# upper.net
KiCad netlist of a schematic drawn in EAGLE
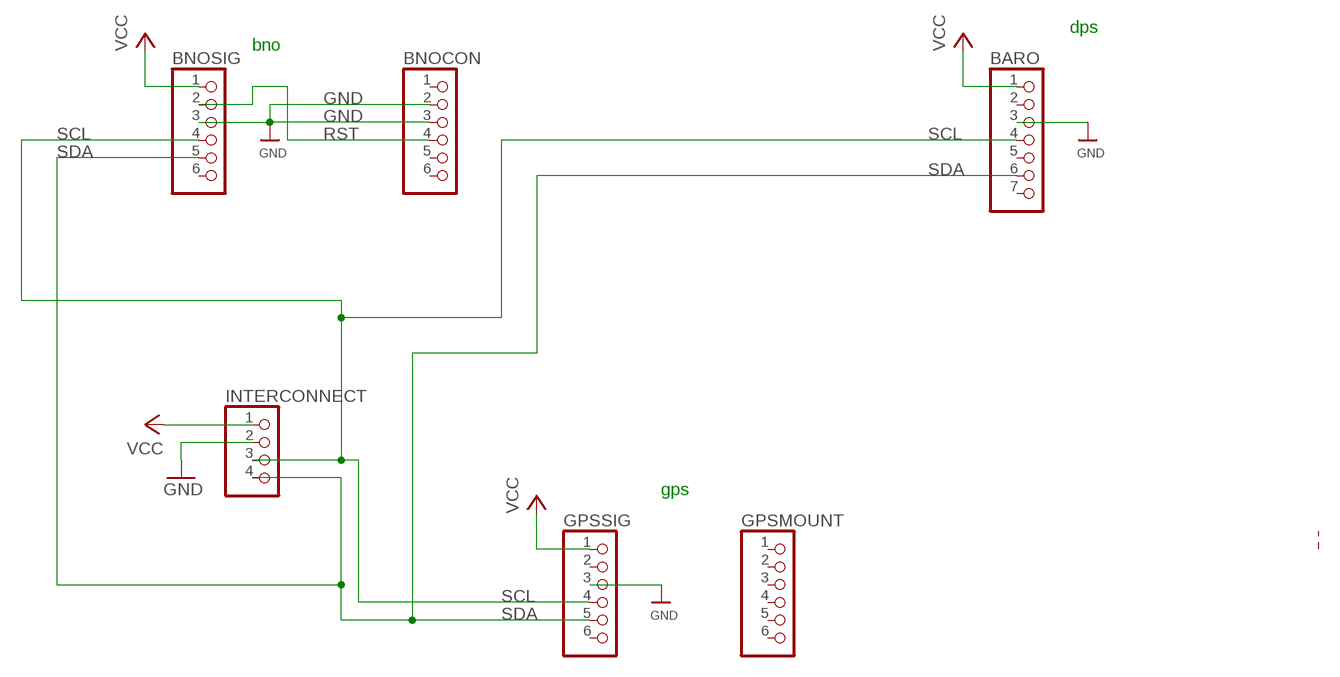
[diagram p0: schematic, sheet 1]

(export (version "E")
  (design (tool "Eeschema 10.0.6"))
  (components
    (comp (ref "BARO")
      (value "HEADER-1X770MIL")
      (footprint "eagle-import:1X07_ROUND_70")
      (libsource (lib "eagle-import") (part "HEADER-1X770MIL"))
    )
    (comp (ref "BNOCON")
      (value "HEADER-1X670MIL")
      (footprint "eagle-import:1X06_ROUND_70")
      (libsource (lib "eagle-import") (part "HEADER-1X670MIL"))
    )
    (comp (ref "BNOSIG")
      (value "HEADER-1X670MIL")
      (footprint "eagle-import:1X06_ROUND_70")
      (libsource (lib "eagle-import") (part "HEADER-1X670MIL"))
    )
    (comp (ref "GPSMOUNT")
      (value "HEADER-1X670MIL")
      (footprint "eagle-import:1X06_ROUND_70")
      (libsource (lib "eagle-import") (part "HEADER-1X670MIL"))
    )
    (comp (ref "GPSSIG")
      (value "HEADER-1X670MIL")
      (footprint "eagle-import:1X06_ROUND_70")
      (libsource (lib "eagle-import") (part "HEADER-1X670MIL"))
    )
    (comp (ref "INTERCONNECT")
      (value "PINHD-1X4")
      (footprint "eagle-import:1X04")
      (libsource (lib "eagle-import") (part "PINHD-1X4"))
    )
  )
  (nets
    (net (code "1") (name "/RST") (class "Default")
      (node (ref "BNOCON") (pin "4") (pinfunction "4_4") (pintype "passive"))
      (node (ref "BNOSIG") (pin "2") (pinfunction "2_2") (pintype "passive"))
    )
    (net (code "2") (name "/SCL") (class "Default")
      (node (ref "BARO") (pin "4") (pinfunction "4_4") (pintype "passive"))
      (node (ref "BNOSIG") (pin "4") (pinfunction "4_4") (pintype "passive"))
      (node (ref "GPSSIG") (pin "4") (pinfunction "4_4") (pintype "passive"))
      (node (ref "INTERCONNECT") (pin "3") (pinfunction "3_3") (pintype "passive"))
    )
    (net (code "3") (name "/SDA") (class "Default")
      (node (ref "BARO") (pin "6") (pinfunction "6_6") (pintype "passive"))
      (node (ref "BNOSIG") (pin "5") (pinfunction "5_5") (pintype "passive"))
      (node (ref "GPSSIG") (pin "5") (pinfunction "5_5") (pintype "passive"))
      (node (ref "INTERCONNECT") (pin "4") (pinfunction "4_4") (pintype "passive"))
    )
    (net (code "4") (name "GND") (class "Default")
      (node (ref "BARO") (pin "3") (pinfunction "3_3") (pintype "passive"))
      (node (ref "BNOCON") (pin "2") (pinfunction "2_2") (pintype "passive"))
      (node (ref "BNOCON") (pin "3") (pinfunction "3_3") (pintype "passive"))
      (node (ref "BNOSIG") (pin "3") (pinfunction "3_3") (pintype "passive"))
      (node (ref "GPSSIG") (pin "3") (pinfunction "3_3") (pintype "passive"))
      (node (ref "INTERCONNECT") (pin "2") (pinfunction "2_2") (pintype "passive"))
    )
    (net (code "5") (name "VCC") (class "Default")
      (node (ref "BARO") (pin "1") (pinfunction "1_1") (pintype "passive"))
      (node (ref "BNOSIG") (pin "1") (pinfunction "1_1") (pintype "passive"))
      (node (ref "GPSSIG") (pin "1") (pinfunction "1_1") (pintype "passive"))
      (node (ref "INTERCONNECT") (pin "1") (pinfunction "1_1") (pintype "passive"))
    )
    (net (code "6") (name "unconnected-(BARO-Pad2)") (class "Default")
      (node (ref "BARO") (pin "2") (pinfunction "2_2") (pintype "passive"))
    )
    (net (code "7") (name "unconnected-(BARO-Pad5)") (class "Default")
      (node (ref "BARO") (pin "5") (pinfunction "5_5") (pintype "passive"))
    )
    (net (code "8") (name "unconnected-(BARO-Pad7)") (class "Default")
      (node (ref "BARO") (pin "7") (pinfunction "7_7") (pintype "passive"))
    )
    (net (code "9") (name "unconnected-(BNOCON-Pad1)") (class "Default")
      (node (ref "BNOCON") (pin "1") (pinfunction "1_1") (pintype "passive"))
    )
    (net (code "10") (name "unconnected-(BNOCON-Pad5)") (class "Default")
      (node (ref "BNOCON") (pin "5") (pinfunction "5_5") (pintype "passive"))
    )
    (net (code "11") (name "unconnected-(BNOCON-Pad6)") (class "Default")
      (node (ref "BNOCON") (pin "6") (pinfunction "6_6") (pintype "passive"))
    )
    (net (code "12") (name "unconnected-(BNOSIG-Pad6)") (class "Default")
      (node (ref "BNOSIG") (pin "6") (pinfunction "6_6") (pintype "passive"))
    )
    (net (code "13") (name "unconnected-(GPSMOUNT-Pad1)") (class "Default")
      (node (ref "GPSMOUNT") (pin "1") (pinfunction "1_1") (pintype "passive"))
    )
    (net (code "14") (name "unconnected-(GPSMOUNT-Pad2)") (class "Default")
      (node (ref "GPSMOUNT") (pin "2") (pinfunction "2_2") (pintype "passive"))
    )
    (net (code "15") (name "unconnected-(GPSMOUNT-Pad3)") (class "Default")
      (node (ref "GPSMOUNT") (pin "3") (pinfunction "3_3") (pintype "passive"))
    )
    (net (code "16") (name "unconnected-(GPSMOUNT-Pad4)") (class "Default")
      (node (ref "GPSMOUNT") (pin "4") (pinfunction "4_4") (pintype "passive"))
    )
    (net (code "17") (name "unconnected-(GPSMOUNT-Pad5)") (class "Default")
      (node (ref "GPSMOUNT") (pin "5") (pinfunction "5_5") (pintype "passive"))
    )
    (net (code "18") (name "unconnected-(GPSMOUNT-Pad6)") (class "Default")
      (node (ref "GPSMOUNT") (pin "6") (pinfunction "6_6") (pintype "passive"))
    )
    (net (code "19") (name "unconnected-(GPSSIG-Pad2)") (class "Default")
      (node (ref "GPSSIG") (pin "2") (pinfunction "2_2") (pintype "passive"))
    )
    (net (code "20") (name "unconnected-(GPSSIG-Pad6)") (class "Default")
      (node (ref "GPSSIG") (pin "6") (pinfunction "6_6") (pintype "passive"))
    )
  )
)
